# NFET_NPN.net
KiCad netlist of a schematic drawn in EAGLE
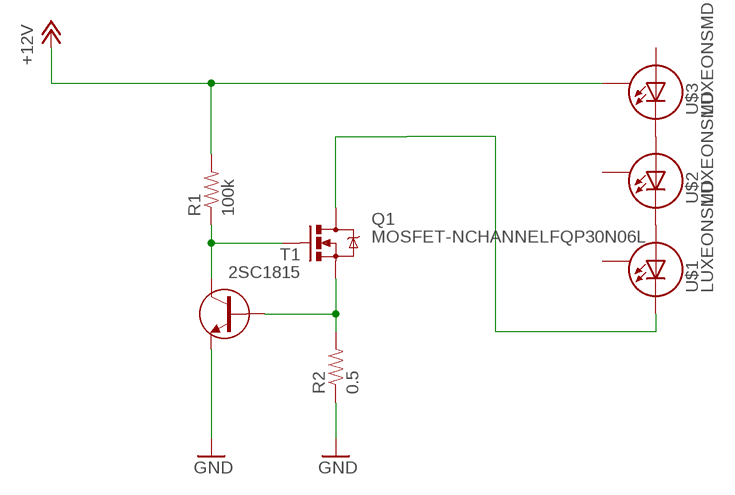
[diagram p0: schematic, sheet 1]

(export (version "E")
  (design (tool "Eeschema 10.0.6"))
  (components
    (comp (ref "Q1")
      (value "MOSFET-NCHANNELFQP30N06L")
      (footprint "eagle-import:TO220V")
      (libsource (lib "eagle-import") (part "MOSFET-NCHANNELFQP30N06L"))
    )
    (comp (ref "R1")
      (value "100k")
      (footprint "eagle-import:AXIAL-0.4")
      (libsource (lib "eagle-import") (part "RESISTORPTH-1/4W"))
    )
    (comp (ref "R2")
      (value "0.5")
      (footprint "eagle-import:AXIAL-0.4")
      (libsource (lib "eagle-import") (part "RESISTORPTH-1/4W"))
    )
    (comp (ref "T1")
      (value "2SC1815")
      (footprint "eagle-import:TO92-ECB")
      (libsource (lib "eagle-import") (part "2SC1815"))
    )
    (comp (ref "U$1")
      (value "LUXEONSMD")
      (footprint "eagle-import:LUXEON")
      (libsource (lib "eagle-import") (part "LUXEONSMD"))
    )
    (comp (ref "U$2")
      (value "LUXEONSMD")
      (footprint "eagle-import:LUXEON")
      (libsource (lib "eagle-import") (part "LUXEONSMD"))
    )
    (comp (ref "U$3")
      (value "LUXEONSMD")
      (footprint "eagle-import:LUXEON")
      (libsource (lib "eagle-import") (part "LUXEONSMD"))
    )
  )
  (nets
    (net (code "1") (name "+12V") (class "Default")
      (node (ref "R1") (pin "P$2") (pinfunction "2_P$2") (pintype "passive"))
      (node (ref "U$3") (pin "S") (pinfunction "S_S") (pintype "bidirectional"))
    )
    (net (code "2") (name "GND") (class "Default")
      (node (ref "R2") (pin "P$1") (pinfunction "1_P$1") (pintype "passive"))
      (node (ref "T1") (pin "1") (pinfunction "E_1") (pintype "passive"))
    )
    (net (code "3") (name "Net-(Q1-D)") (class "Default")
      (node (ref "Q1") (pin "2") (pinfunction "D_2") (pintype "passive"))
      (node (ref "U$1") (pin "C") (pinfunction "C_C") (pintype "passive"))
    )
    (net (code "4") (name "Net-(Q1-G)") (class "Default")
      (node (ref "Q1") (pin "1") (pinfunction "G_1") (pintype "passive"))
      (node (ref "R1") (pin "P$1") (pinfunction "1_P$1") (pintype "passive"))
      (node (ref "T1") (pin "2") (pinfunction "C_2") (pintype "passive"))
    )
    (net (code "5") (name "Net-(Q1-S)") (class "Default")
      (node (ref "Q1") (pin "3") (pinfunction "S_3") (pintype "passive"))
      (node (ref "R2") (pin "P$2") (pinfunction "2_P$2") (pintype "passive"))
      (node (ref "T1") (pin "3") (pinfunction "B_3") (pintype "passive"))
    )
    (net (code "6") (name "Net-(U$1-PadA)") (class "Default")
      (node (ref "U$1") (pin "A") (pinfunction "A_A") (pintype "passive"))
      (node (ref "U$2") (pin "C") (pinfunction "C_C") (pintype "passive"))
    )
    (net (code "7") (name "Net-(U$2-PadA)") (class "Default")
      (node (ref "U$2") (pin "A") (pinfunction "A_A") (pintype "passive"))
      (node (ref "U$3") (pin "C") (pinfunction "C_C") (pintype "passive"))
    )
    (net (code "8") (name "unconnected-(U$1-PadS)") (class "Default")
      (node (ref "U$1") (pin "S") (pinfunction "S_S") (pintype "bidirectional"))
    )
    (net (code "9") (name "unconnected-(U$2-PadS)") (class "Default")
      (node (ref "U$2") (pin "S") (pinfunction "S_S") (pintype "bidirectional"))
    )
    (net (code "10") (name "unconnected-(U$3-PadA)") (class "Default")
      (node (ref "U$3") (pin "A") (pinfunction "A_A") (pintype "passive"))
    )
  )
)
